# File_Nguyen_Ly.net
KiCad netlist of a schematic drawn in Altium Designer
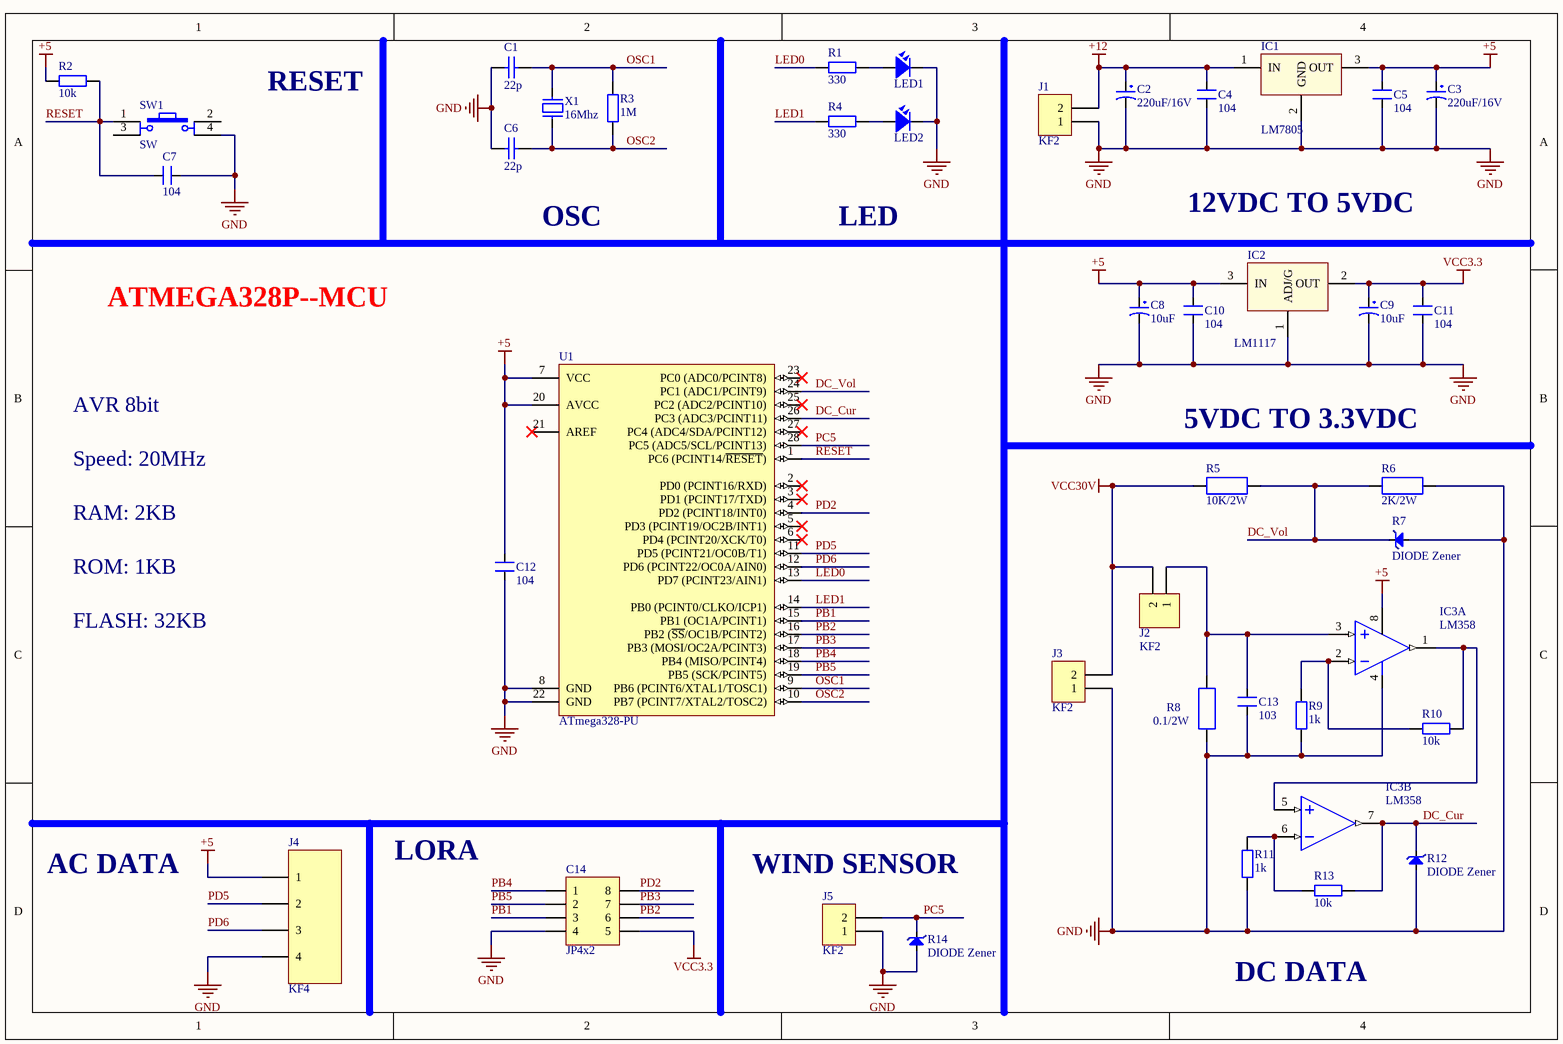
[diagram p0: File_Nguyen_Ly.SchDoc]

(export (version "E")
  (design (tool "Eeschema 10.0.6"))
  (components
    (comp (ref "C1")
      (value "22p")
      (footprint "Tu-ceramic")
      (description "Capacitor")
      (fields (field (name "Comment") "Capacitor Ceramic") (field (name "PUBLISHER") "Altium Limited"))
      (libsource (lib "Cty1") (part "CapDecop"))
    )
    (comp (ref "C2")
      (value "220uF/16V")
      (footprint "CP1.5/3.4")
      (description "Cap 1000uF/16V - 220uF/50V")
      (libsource (lib "syhaunguyen") (part "CP4"))
    )
    (comp (ref "C3")
      (value "220uF/16V")
      (footprint "CP1.5/3.4")
      (description "Cap 1000uF/16V - 220uF/50V")
      (libsource (lib "syhaunguyen") (part "CP4"))
    )
    (comp (ref "C4")
      (value "104")
      (footprint "CN2")
      (description "Cap np 104 => 105pF")
      (libsource (lib "syhaunguyen") (part "CN2"))
    )
    (comp (ref "C5")
      (value "104")
      (footprint "CN2")
      (description "Cap np 104 => 105pF")
      (libsource (lib "syhaunguyen") (part "CN2"))
    )
    (comp (ref "C6")
      (value "22p")
      (footprint "Tu-ceramic")
      (description "Capacitor")
      (fields (field (name "Comment") "Capacitor Ceramic") (field (name "PUBLISHER") "Altium Limited"))
      (libsource (lib "Cty1") (part "CapDecop"))
    )
    (comp (ref "C7")
      (value "104")
      (footprint "CN2")
      (description "Cap np 104 => 105pF")
      (libsource (lib "syhaunguyen") (part "CN2"))
    )
    (comp (ref "C8")
      (value "10uF")
      (footprint "CP1/2")
      (description "Cap P  0,1uF < 22uF , 16 - 50V")
      (libsource (lib "syhaunguyen") (part "CP1"))
    )
    (comp (ref "C9")
      (value "10uF")
      (footprint "CP1/2")
      (description "Cap P  0,1uF < 22uF , 16 - 50V")
      (libsource (lib "syhaunguyen") (part "CP1"))
    )
    (comp (ref "C10")
      (value "104")
      (footprint "CN2")
      (description "Cap np 104 => 105pF")
      (libsource (lib "syhaunguyen") (part "CN2"))
    )
    (comp (ref "C11")
      (value "104")
      (footprint "CN2")
      (description "Cap np 104 => 105pF")
      (libsource (lib "syhaunguyen") (part "CN2"))
    )
    (comp (ref "C12")
      (value "104")
      (footprint "CN2")
      (description "Cap np 104 => 105pF")
      (libsource (lib "syhaunguyen") (part "CN2"))
    )
    (comp (ref "C13")
      (value "103")
      (footprint "CN1.5")
      (description "Cap np 682pF => 104pF")
      (libsource (lib "syhaunguyen") (part "CN1.5"))
    )
    (comp (ref "C14")
      (value "JP4x2")
      (footprint "JP4-C2T")
      (description "WR-PHD 2.54 mm Dual Socket Header")
      (fields
        (field (name "MANUFACTURER") "Würth Elektronik eiSos GmbH")
        (field (name "PARTNO") "61300821821")
        (field (name "CREATED BY") "Karrer Zheng")
      )
      (libsource (lib "LIBRARY") (part "JP4x2"))
    )
    (comp (ref "IC1")
      (value "LM7805")
      (footprint "QTO-220")
      (description "On ap +, from + 5 to + 24VDC")
      (libsource (lib "syhaunguyen") (part "LM78xx"))
    )
    (comp (ref "IC2")
      (value "LM1117")
      (footprint "SOT223-4N")
      (description "Available in 1.8V, 2.5V, 2.85V, 3.3V, 5V, and  Adjustable Versions")
      (libsource (lib "syhaunguyen") (part "LM1117"))
    )
    (comp (ref "IC3")
      (value "LM358")
      (footprint "DIP8/W0.3")
      (description "Low-Power Dual Operational Amplifier")
      (libsource (lib "syhaunguyen") (part "LM358"))
    )
    (comp (ref "J1")
      (value "KF2")
      (footprint "KF2-5.08")
      (fields
        (field (name "MANUFACTURER") "Würth Elektronik eiSos GmbH")
        (field (name "PARTNO") "691103110002")
        (field (name "CREATED BY") "Karrer Zheng")
      )
      (libsource (lib "LIBRARY") (part "KF2"))
    )
    (comp (ref "J2")
      (value "KF2")
      (footprint "KF2-5.08")
      (fields
        (field (name "MANUFACTURER") "Würth Elektronik eiSos GmbH")
        (field (name "PARTNO") "691103110002")
        (field (name "CREATED BY") "Karrer Zheng")
      )
      (libsource (lib "") (part "KF2_1"))
    )
    (comp (ref "J3")
      (value "KF2")
      (footprint "KF2-5.08")
      (fields
        (field (name "MANUFACTURER") "Würth Elektronik eiSos GmbH")
        (field (name "PARTNO") "691103110002")
        (field (name "CREATED BY") "Karrer Zheng")
      )
      (libsource (lib "LIBRARY") (part "KF2"))
    )
    (comp (ref "J4")
      (value "KF4")
      (footprint "KF4-5.08")
      (fields
        (field (name "MANUFACTURER") "Würth Elektronik eiSos GmbH")
        (field (name "PARTNO") "691133710004")
        (field (name "CREATED BY") "Baojun Chen")
      )
      (libsource (lib "LIBRARY") (part "KF4"))
    )
    (comp (ref "J5")
      (value "KF2")
      (footprint "KF2-5.08")
      (fields
        (field (name "MANUFACTURER") "Würth Elektronik eiSos GmbH")
        (field (name "PARTNO") "691103110002")
        (field (name "CREATED BY") "Karrer Zheng")
      )
      (libsource (lib "LIBRARY") (part "KF2"))
    )
    (comp (ref "LED1")
      (value "LED")
      (footprint "LED-5-Yellow")
      (description "LED Single colour Green and Red")
      (libsource (lib "syhaunguyen") (part "LED"))
    )
    (comp (ref "LED2")
      (value "LED")
      (footprint "LED-5-BLUE")
      (description "LED Single colour Green and Red")
      (libsource (lib "syhaunguyen") (part "LED"))
    )
    (comp (ref "R1")
      (value "330")
      (footprint "R1/4W")
      (description "Resistor 1/4W")
      (libsource (lib "syhaunguyen") (part "R1/4W"))
    )
    (comp (ref "R2")
      (value "10k")
      (footprint "R1/4W")
      (description "Resistor 1/4W")
      (libsource (lib "syhaunguyen") (part "R1/4W"))
    )
    (comp (ref "R3")
      (value "1M")
      (footprint "R1/4W")
      (description "Resistor 1/4W")
      (libsource (lib "syhaunguyen") (part "R1/4W"))
    )
    (comp (ref "R4")
      (value "330")
      (footprint "R1/4W")
      (description "Resistor 1/4W")
      (libsource (lib "syhaunguyen") (part "R1/4W"))
    )
    (comp (ref "R5")
      (value "10K/2W")
      (footprint "R2W")
      (description "Resistor 2W")
      (libsource (lib "syhaunguyen") (part "R2W"))
    )
    (comp (ref "R6")
      (value "2K/2W")
      (footprint "R2W")
      (description "Resistor 2W")
      (libsource (lib "syhaunguyen") (part "R2W"))
    )
    (comp (ref "R7")
      (value "DIODE Zener")
      (footprint "DIO-2A - LONG")
      (description "Zenner")
      (libsource (lib "LIBRARY") (part "DIODE Zener"))
    )
    (comp (ref "R8")
      (value "0.1/2W")
      (footprint "R2W")
      (description "Resistor 2W")
      (libsource (lib "syhaunguyen") (part "R2W"))
    )
    (comp (ref "R9")
      (value "1k")
      (footprint "R1/4W")
      (description "Resistor 1/4W")
      (libsource (lib "syhaunguyen") (part "R1/4W"))
    )
    (comp (ref "R10")
      (value "10k")
      (footprint "R1/4W")
      (description "Resistor 1/4W")
      (libsource (lib "syhaunguyen") (part "R1/4W"))
    )
    (comp (ref "R11")
      (value "1k")
      (footprint "R1/4W")
      (description "Resistor 1/4W")
      (libsource (lib "syhaunguyen") (part "R1/4W"))
    )
    (comp (ref "R12")
      (value "DIODE Zener")
      (footprint "DIO-2A - LONG")
      (description "Zenner")
      (libsource (lib "LIBRARY") (part "DIODE Zener"))
    )
    (comp (ref "R13")
      (value "10k")
      (footprint "R1/4W")
      (description "Resistor 1/4W")
      (libsource (lib "syhaunguyen") (part "R1/4W"))
    )
    (comp (ref "R14")
      (value "DIODE Zener")
      (footprint "DIO-2A - LONG")
      (description "Zenner")
      (libsource (lib "LIBRARY") (part "DIODE Zener"))
    )
    (comp (ref "SW1")
      (value "SW")
      (footprint "SW4")
      (description "Switch button 4 pin")
      (libsource (lib "syhaunguyen") (part "SW4"))
    )
    (comp (ref "U1")
      (value "ATmega328-PU")
      (footprint "DIP28")
      (fields (field (name "PUBLISHER") "Altium Limited"))
      (libsource (lib "LIBRARY") (part "ATmega328-PU"))
    )
    (comp (ref "X1")
      (value "16Mhz")
      (footprint "XT2")
      (description "Crystal For all Crystal 2pin.")
      (libsource (lib "syhaunguyen") (part "XT2"))
    )
  )
  (nets
    (net (code "1") (name "+5") (class "Default")
      (node (ref "C10") (pin "2") (pinfunction "2_2") (pintype "passive"))
      (node (ref "C12") (pin "2") (pinfunction "2_2") (pintype "passive"))
      (node (ref "C3") (pin "1") (pinfunction "1_1") (pintype "passive"))
      (node (ref "C5") (pin "2") (pinfunction "2_2") (pintype "passive"))
      (node (ref "C8") (pin "1") (pinfunction "1_1") (pintype "passive"))
      (node (ref "IC1") (pin "3") (pinfunction "OUT_3") (pintype "passive"))
      (node (ref "IC2") (pin "3") (pinfunction "IN_3") (pintype "passive"))
      (node (ref "IC3") (pin "8") (pinfunction "+V_8") (pintype "passive"))
      (node (ref "J4") (pin "1") (pinfunction "1_1") (pintype "passive"))
      (node (ref "R2") (pin "1") (pinfunction "1_1") (pintype "passive"))
      (node (ref "U1") (pin "20") (pinfunction "AVCC_20") (pintype "power_in"))
      (node (ref "U1") (pin "7") (pinfunction "VCC_7") (pintype "power_in"))
    )
    (net (code "2") (name "+12") (class "Default")
      (node (ref "C2") (pin "1") (pinfunction "1_1") (pintype "passive"))
      (node (ref "C4") (pin "2") (pinfunction "2_2") (pintype "passive"))
      (node (ref "IC1") (pin "1") (pinfunction "IN_1") (pintype "passive"))
      (node (ref "J1") (pin "2") (pinfunction "2_2") (pintype "passive"))
    )
    (net (code "3") (name "/DC_Cur") (class "Default")
      (node (ref "IC3") (pin "7") (pinfunction "OUT_7") (pintype "output"))
      (node (ref "R12") (pin "2") (pinfunction "K_2") (pintype "passive"))
      (node (ref "R13") (pin "1") (pinfunction "1_1") (pintype "passive"))
      (node (ref "U1") (pin "26") (pinfunction "PC3_(ADC3/PCINT11)_26") (pintype "bidirectional"))
    )
    (net (code "4") (name "/DC_Vol") (class "Default")
      (node (ref "R5") (pin "2") (pinfunction "2_2") (pintype "passive"))
      (node (ref "R6") (pin "1") (pinfunction "1_1") (pintype "passive"))
      (node (ref "R7") (pin "2") (pinfunction "K_2") (pintype "passive"))
      (node (ref "U1") (pin "24") (pinfunction "PC1_(ADC1/PCINT9)_24") (pintype "bidirectional"))
    )
    (net (code "5") (name "/LED0") (class "Default")
      (node (ref "R1") (pin "2") (pinfunction "2_2") (pintype "passive"))
      (node (ref "U1") (pin "13") (pinfunction "PD7_(PCINT23/AIN1)_13") (pintype "bidirectional"))
    )
    (net (code "6") (name "/LED1") (class "Default")
      (node (ref "R4") (pin "2") (pinfunction "2_2") (pintype "passive"))
      (node (ref "U1") (pin "14") (pinfunction "PB0_(PCINT0/CLKO/ICP1)_14") (pintype "bidirectional"))
    )
    (net (code "7") (name "/OSC1") (class "Default")
      (node (ref "C1") (pin "2") (pinfunction "2_2") (pintype "passive"))
      (node (ref "R3") (pin "2") (pinfunction "2_2") (pintype "passive"))
      (node (ref "U1") (pin "9") (pinfunction "PB6_(PCINT6/XTAL1/TOSC1)_9") (pintype "bidirectional"))
      (node (ref "X1") (pin "2") (pinfunction "2_2") (pintype "passive"))
    )
    (net (code "8") (name "/OSC2") (class "Default")
      (node (ref "C6") (pin "2") (pinfunction "2_2") (pintype "passive"))
      (node (ref "R3") (pin "1") (pinfunction "1_1") (pintype "passive"))
      (node (ref "U1") (pin "10") (pinfunction "PB7_(PCINT7/XTAL2/TOSC2)_10") (pintype "bidirectional"))
      (node (ref "X1") (pin "1") (pinfunction "1_1") (pintype "passive"))
    )
    (net (code "9") (name "/PB1") (class "Default")
      (node (ref "C14") (pin "3") (pinfunction "3_3") (pintype "passive"))
      (node (ref "U1") (pin "15") (pinfunction "PB1_(OC1A/PCINT1)_15") (pintype "bidirectional"))
    )
    (net (code "10") (name "/PB2") (class "Default")
      (node (ref "C14") (pin "6") (pinfunction "6_6") (pintype "passive"))
      (node (ref "U1") (pin "16") (pinfunction "PB2_(~{SS}/OC1B/PCINT2)_16") (pintype "bidirectional"))
    )
    (net (code "11") (name "/PB3") (class "Default")
      (node (ref "C14") (pin "7") (pinfunction "7_7") (pintype "passive"))
      (node (ref "U1") (pin "17") (pinfunction "PB3_(MOSI/OC2A/PCINT3)_17") (pintype "bidirectional"))
    )
    (net (code "12") (name "/PB4") (class "Default")
      (node (ref "C14") (pin "1") (pinfunction "1_1") (pintype "passive"))
      (node (ref "U1") (pin "18") (pinfunction "PB4_(MISO/PCINT4)_18") (pintype "bidirectional"))
    )
    (net (code "13") (name "/PB5") (class "Default")
      (node (ref "C14") (pin "2") (pinfunction "2_2") (pintype "passive"))
      (node (ref "U1") (pin "19") (pinfunction "PB5_(SCK/PCINT5)_19") (pintype "bidirectional"))
    )
    (net (code "14") (name "/PC5") (class "Default")
      (node (ref "J5") (pin "2") (pinfunction "2_2") (pintype "passive"))
      (node (ref "R14") (pin "2") (pinfunction "K_2") (pintype "passive"))
      (node (ref "U1") (pin "28") (pinfunction "PC5_(ADC5/SCL/PCINT13)_28") (pintype "bidirectional"))
    )
    (net (code "15") (name "/PD2") (class "Default")
      (node (ref "C14") (pin "8") (pinfunction "8_8") (pintype "passive"))
      (node (ref "U1") (pin "4") (pinfunction "PD2_(PCINT18/INT0)_4") (pintype "bidirectional"))
    )
    (net (code "16") (name "/PD5") (class "Default")
      (node (ref "J4") (pin "2") (pinfunction "2_2") (pintype "passive"))
      (node (ref "U1") (pin "11") (pinfunction "PD5_(PCINT21/OC0B/T1)_11") (pintype "bidirectional"))
    )
    (net (code "17") (name "/PD6") (class "Default")
      (node (ref "J4") (pin "3") (pinfunction "3_3") (pintype "passive"))
      (node (ref "U1") (pin "12") (pinfunction "PD6_(PCINT22/OC0A/AIN0)_12") (pintype "bidirectional"))
    )
    (net (code "18") (name "/RESET") (class "Default")
      (node (ref "C7") (pin "1") (pinfunction "1_1") (pintype "passive"))
      (node (ref "R2") (pin "2") (pinfunction "2_2") (pintype "passive"))
      (node (ref "SW1") (pin "1") (pintype "passive"))
      (node (ref "U1") (pin "1") (pinfunction "PC6_(PCINT14/~{RESET})_1") (pintype "bidirectional"))
    )
    (net (code "19") (name "GND") (class "Default")
      (node (ref "C1") (pin "1") (pinfunction "1_1") (pintype "passive"))
      (node (ref "C10") (pin "1") (pinfunction "1_1") (pintype "passive"))
      (node (ref "C11") (pin "1") (pinfunction "1_1") (pintype "passive"))
      (node (ref "C12") (pin "1") (pinfunction "1_1") (pintype "passive"))
      (node (ref "C13") (pin "1") (pinfunction "1_1") (pintype "passive"))
      (node (ref "C14") (pin "4") (pinfunction "4_4") (pintype "passive"))
      (node (ref "C2") (pin "2") (pinfunction "2_2") (pintype "passive"))
      (node (ref "C3") (pin "2") (pinfunction "2_2") (pintype "passive"))
      (node (ref "C4") (pin "1") (pinfunction "1_1") (pintype "passive"))
      (node (ref "C5") (pin "1") (pinfunction "1_1") (pintype "passive"))
      (node (ref "C6") (pin "1") (pinfunction "1_1") (pintype "passive"))
      (node (ref "C7") (pin "2") (pinfunction "2_2") (pintype "passive"))
      (node (ref "C8") (pin "2") (pinfunction "2_2") (pintype "passive"))
      (node (ref "C9") (pin "2") (pinfunction "2_2") (pintype "passive"))
      (node (ref "IC1") (pin "2") (pinfunction "GND_2") (pintype "passive"))
      (node (ref "IC2") (pin "1") (pinfunction "ADJ/G_1") (pintype "passive"))
      (node (ref "IC3") (pin "4") (pinfunction "-V_4") (pintype "passive"))
      (node (ref "J1") (pin "1") (pinfunction "1_1") (pintype "passive"))
      (node (ref "J3") (pin "1") (pinfunction "1_1") (pintype "passive"))
      (node (ref "J4") (pin "4") (pinfunction "4_4") (pintype "passive"))
      (node (ref "J5") (pin "1") (pinfunction "1_1") (pintype "passive"))
      (node (ref "LED1") (pin "2") (pinfunction "2_2") (pintype "passive"))
      (node (ref "LED2") (pin "2") (pinfunction "2_2") (pintype "passive"))
      (node (ref "R11") (pin "2") (pinfunction "2_2") (pintype "passive"))
      (node (ref "R12") (pin "1") (pinfunction "A_1") (pintype "passive"))
      (node (ref "R14") (pin "1") (pinfunction "A_1") (pintype "passive"))
      (node (ref "R6") (pin "2") (pinfunction "2_2") (pintype "passive"))
      (node (ref "R7") (pin "1") (pinfunction "A_1") (pintype "passive"))
      (node (ref "R8") (pin "1") (pinfunction "1_1") (pintype "passive"))
      (node (ref "R9") (pin "2") (pinfunction "2_2") (pintype "passive"))
      (node (ref "SW1") (pin "4") (pintype "passive"))
      (node (ref "U1") (pin "22") (pinfunction "GND_22") (pintype "power_in"))
      (node (ref "U1") (pin "8") (pinfunction "GND_8") (pintype "power_in"))
    )
    (net (code "20") (name "Net-(IC3A-IN+)") (class "Default")
      (node (ref "C13") (pin "2") (pinfunction "2_2") (pintype "passive"))
      (node (ref "IC3") (pin "3") (pinfunction "IN+_3") (pintype "input"))
      (node (ref "J2") (pin "1") (pinfunction "1_1") (pintype "passive"))
      (node (ref "R8") (pin "2") (pinfunction "2_2") (pintype "passive"))
    )
    (net (code "21") (name "Net-(IC3A-IN-)") (class "Default")
      (node (ref "IC3") (pin "2") (pinfunction "IN-_2") (pintype "input"))
      (node (ref "R10") (pin "2") (pinfunction "2_2") (pintype "passive"))
      (node (ref "R9") (pin "1") (pinfunction "1_1") (pintype "passive"))
    )
    (net (code "22") (name "Net-(IC3A-OUT)") (class "Default")
      (node (ref "IC3") (pin "1") (pinfunction "OUT_1") (pintype "output"))
      (node (ref "IC3") (pin "5") (pinfunction "IN+_5") (pintype "input"))
      (node (ref "R10") (pin "1") (pinfunction "1_1") (pintype "passive"))
    )
    (net (code "23") (name "Net-(IC3B-IN-)") (class "Default")
      (node (ref "IC3") (pin "6") (pinfunction "IN-_6") (pintype "input"))
      (node (ref "R11") (pin "1") (pinfunction "1_1") (pintype "passive"))
      (node (ref "R13") (pin "2") (pinfunction "2_2") (pintype "passive"))
    )
    (net (code "24") (name "Net-(LED1-Pad1)") (class "Default")
      (node (ref "LED1") (pin "1") (pinfunction "1_1") (pintype "passive"))
      (node (ref "R1") (pin "1") (pinfunction "1_1") (pintype "passive"))
    )
    (net (code "25") (name "Net-(LED2-Pad1)") (class "Default")
      (node (ref "LED2") (pin "1") (pinfunction "1_1") (pintype "passive"))
      (node (ref "R4") (pin "1") (pinfunction "1_1") (pintype "passive"))
    )
    (net (code "26") (name "VCC3.3") (class "Default")
      (node (ref "C11") (pin "2") (pinfunction "2_2") (pintype "passive"))
      (node (ref "C14") (pin "5") (pinfunction "5_5") (pintype "passive"))
      (node (ref "C9") (pin "1") (pinfunction "1_1") (pintype "passive"))
      (node (ref "IC2") (pin "2") (pinfunction "OUT_2") (pintype "passive"))
    )
    (net (code "27") (name "VCC30V") (class "Default")
      (node (ref "J2") (pin "2") (pinfunction "2_2") (pintype "passive"))
      (node (ref "J3") (pin "2") (pinfunction "2_2") (pintype "passive"))
      (node (ref "R5") (pin "1") (pinfunction "1_1") (pintype "passive"))
    )
    (net (code "28") (name "unconnected-(SW1-Pad2)") (class "Default")
      (node (ref "SW1") (pin "2") (pintype "passive"))
    )
    (net (code "29") (name "unconnected-(SW1-Pad3)") (class "Default")
      (node (ref "SW1") (pin "3") (pintype "passive"))
    )
    (net (code "30") (name "unconnected-(U1-AREF-Pad21)") (class "Default")
      (node (ref "U1") (pin "21") (pinfunction "AREF_21") (pintype "power_in+no_connect"))
    )
    (net (code "31") (name "unconnected-(U1-PC0_(ADC0{slash}PCINT8)-Pad23)") (class "Default")
      (node (ref "U1") (pin "23") (pinfunction "PC0_(ADC0/PCINT8)_23") (pintype "bidirectional+no_connect"))
    )
    (net (code "32") (name "unconnected-(U1-PC2_(ADC2{slash}PCINT10)-Pad25)") (class "Default")
      (node (ref "U1") (pin "25") (pinfunction "PC2_(ADC2/PCINT10)_25") (pintype "bidirectional+no_connect"))
    )
    (net (code "33") (name "unconnected-(U1-PC4_(ADC4{slash}SDA{slash}PCINT12)-Pad27)") (class "Default")
      (node (ref "U1") (pin "27") (pinfunction "PC4_(ADC4/SDA/PCINT12)_27") (pintype "bidirectional+no_connect"))
    )
    (net (code "34") (name "unconnected-(U1-PD0_(PCINT16{slash}RXD)-Pad2)") (class "Default")
      (node (ref "U1") (pin "2") (pinfunction "PD0_(PCINT16/RXD)_2") (pintype "bidirectional+no_connect"))
    )
    (net (code "35") (name "unconnected-(U1-PD1_(PCINT17{slash}TXD)-Pad3)") (class "Default")
      (node (ref "U1") (pin "3") (pinfunction "PD1_(PCINT17/TXD)_3") (pintype "bidirectional+no_connect"))
    )
    (net (code "36") (name "unconnected-(U1-PD3_(PCINT19{slash}OC2B{slash}INT1)-Pad5)") (class "Default")
      (node (ref "U1") (pin "5") (pinfunction "PD3_(PCINT19/OC2B/INT1)_5") (pintype "bidirectional+no_connect"))
    )
    (net (code "37") (name "unconnected-(U1-PD4_(PCINT20{slash}XCK{slash}T0)-Pad6)") (class "Default")
      (node (ref "U1") (pin "6") (pinfunction "PD4_(PCINT20/XCK/T0)_6") (pintype "bidirectional+no_connect"))
    )
  )
)
